# Sheet1.net
KiCad netlist of a schematic drawn in Altium Designer
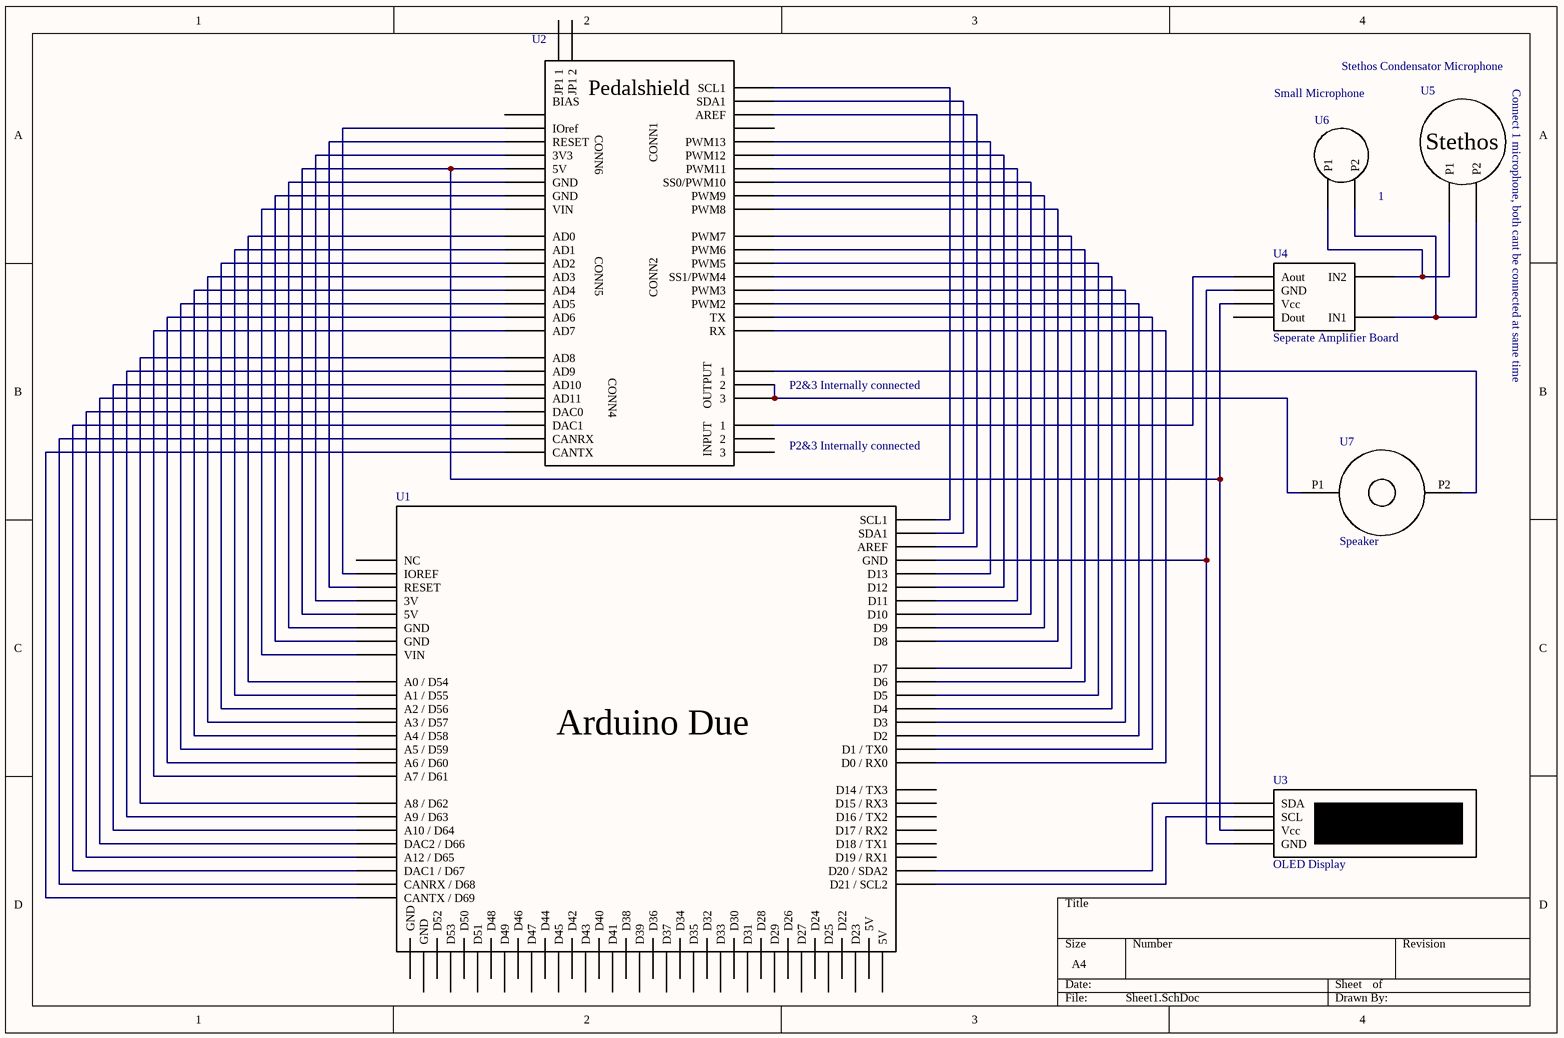
[diagram p0: Sheet1.SchDoc]

(export (version "E")
  (design (tool "Eeschema 10.0.6"))
  (components
    (comp (ref "U1") (value "Arduino Due") (libsource (lib "Schlib1") (part "Arduino Due")))
    (comp (ref "U2") (value "1") (libsource (lib "Schlib1") (part "Pedalshield")))
    (comp (ref "U3") (value "OLED Display") (libsource (lib "Schlib1") (part "OLED Display")))
    (comp (ref "U4")
      (value "Seperate Amplifier Board")
      (libsource (lib "Schlib1") (part "Seperate Amplifier Board"))
    )
    (comp (ref "U5")
      (value "Stethos Condensator Microphone")
      (libsource (lib "Schlib1") (part "Stethos Condensator Microphone"))
    )
    (comp (ref "U6") (value "Small Microphone") (libsource (lib "Schlib1") (part "Small Microphone")))
    (comp (ref "U7") (value "Speaker") (libsource (lib "Schlib1") (part "Speaker")))
  )
  (nets
    (net (code "1") (name "Net-(U1-3V)") (class "Default")
      (node (ref "U1") (pin "SDA5") (pinfunction "3V_SDA5") (pintype "passive"))
      (node (ref "U2") (pin "SDA103") (pinfunction "3V3_SDA103") (pintype "passive"))
    )
    (net (code "2") (name "Net-(U1-A0_{slash}_D54)") (class "Default")
      (node (ref "U1") (pin "SDA11") (pinfunction "A0_/_D54_SDA11") (pintype "passive"))
      (node (ref "U2") (pin "SDA108") (pinfunction "AD0_SDA108") (pintype "passive"))
    )
    (net (code "3") (name "Net-(U1-A1_{slash}_D55)") (class "Default")
      (node (ref "U1") (pin "SDA12") (pinfunction "A1_/_D55_SDA12") (pintype "passive"))
      (node (ref "U2") (pin "SDA109") (pinfunction "AD1_SDA109") (pintype "passive"))
    )
    (net (code "4") (name "Net-(U1-A2_{slash}_D56)") (class "Default")
      (node (ref "U1") (pin "SDA13") (pinfunction "A2_/_D56_SDA13") (pintype "passive"))
      (node (ref "U2") (pin "SDA110") (pinfunction "AD2_SDA110") (pintype "passive"))
    )
    (net (code "5") (name "Net-(U1-A3_{slash}_D57)") (class "Default")
      (node (ref "U1") (pin "SDA14") (pinfunction "A3_/_D57_SDA14") (pintype "passive"))
      (node (ref "U2") (pin "SDA111") (pinfunction "AD3_SDA111") (pintype "passive"))
    )
    (net (code "6") (name "Net-(U1-A4_{slash}_D58)") (class "Default")
      (node (ref "U1") (pin "SDA15") (pinfunction "A4_/_D58_SDA15") (pintype "passive"))
      (node (ref "U2") (pin "SDA112") (pinfunction "AD4_SDA112") (pintype "passive"))
    )
    (net (code "7") (name "Net-(U1-A5_{slash}_D59)") (class "Default")
      (node (ref "U1") (pin "SDA16") (pinfunction "A5_/_D59_SDA16") (pintype "passive"))
      (node (ref "U2") (pin "SDA113") (pinfunction "AD5_SDA113") (pintype "passive"))
    )
    (net (code "8") (name "Net-(U1-A6_{slash}_D60)") (class "Default")
      (node (ref "U1") (pin "SDA17") (pinfunction "A6_/_D60_SDA17") (pintype "passive"))
      (node (ref "U2") (pin "SDA114") (pinfunction "AD6_SDA114") (pintype "passive"))
    )
    (net (code "9") (name "Net-(U1-A7_{slash}_D61)") (class "Default")
      (node (ref "U1") (pin "SDA18") (pinfunction "A7_/_D61_SDA18") (pintype "passive"))
      (node (ref "U2") (pin "SDA115") (pinfunction "AD7_SDA115") (pintype "passive"))
    )
    (net (code "10") (name "Net-(U1-A8_{slash}_D62)") (class "Default")
      (node (ref "U1") (pin "SDA20") (pinfunction "A8_/_D62_SDA20") (pintype "passive"))
      (node (ref "U2") (pin "SDA97") (pinfunction "AD8_SDA97") (pintype "passive"))
    )
    (net (code "11") (name "Net-(U1-A9_{slash}_D63)") (class "Default")
      (node (ref "U1") (pin "SDA21") (pinfunction "A9_/_D63_SDA21") (pintype "passive"))
      (node (ref "U2") (pin "SDA96") (pinfunction "AD9_SDA96") (pintype "passive"))
    )
    (net (code "12") (name "Net-(U1-A10_{slash}_D64)") (class "Default")
      (node (ref "U1") (pin "SDA22") (pinfunction "A10_/_D64_SDA22") (pintype "passive"))
      (node (ref "U2") (pin "SDA95") (pinfunction "AD10_SDA95") (pintype "passive"))
    )
    (net (code "13") (name "Net-(U1-A12_{slash}_D65)") (class "Default")
      (node (ref "U1") (pin "SDA24") (pinfunction "A12_/_D65_SDA24") (pintype "passive"))
      (node (ref "U2") (pin "SDA93") (pinfunction "DAC0_SDA93") (pintype "passive"))
    )
    (net (code "14") (name "Net-(U1-CANRX_{slash}_D68)") (class "Default")
      (node (ref "U1") (pin "SDA26") (pinfunction "CANRX_/_D68_SDA26") (pintype "passive"))
      (node (ref "U2") (pin "SDA91") (pinfunction "CANRX_SDA91") (pintype "passive"))
    )
    (net (code "15") (name "Net-(U1-CANTX_{slash}_D69)") (class "Default")
      (node (ref "U1") (pin "SDA27") (pinfunction "CANTX_/_D69_SDA27") (pintype "passive"))
      (node (ref "U2") (pin "SDA90") (pinfunction "CANTX_SDA90") (pintype "passive"))
    )
    (net (code "16") (name "Net-(U1-D0_{slash}_RX0)") (class "Default")
      (node (ref "U1") (pin "29") (pinfunction "D0_/_RX0_29") (pintype "passive"))
      (node (ref "U2") (pin "SDA88") (pinfunction "RX_SDA88") (pintype "passive"))
    )
    (net (code "17") (name "Net-(U1-D1_{slash}_TX0)") (class "Default")
      (node (ref "U1") (pin "28") (pinfunction "D1_/_TX0_28") (pintype "passive"))
      (node (ref "U2") (pin "SDA87") (pinfunction "TX_SDA87") (pintype "passive"))
    )
    (net (code "18") (name "Net-(U1-D2)") (class "Default")
      (node (ref "U1") (pin "27") (pinfunction "D2_27") (pintype "passive"))
      (node (ref "U2") (pin "SDA118") (pinfunction "PWM2_SDA118") (pintype "passive"))
    )
    (net (code "19") (name "Net-(U1-D3)") (class "Default")
      (node (ref "U1") (pin "26") (pinfunction "D3_26") (pintype "passive"))
      (node (ref "U2") (pin "SDA86") (pinfunction "PWM3_SDA86") (pintype "passive"))
    )
    (net (code "20") (name "Net-(U1-D4)") (class "Default")
      (node (ref "U1") (pin "25") (pinfunction "D4_25") (pintype "passive"))
      (node (ref "U2") (pin "SDA85") (pinfunction "SS1/PWM4_SDA85") (pintype "passive"))
    )
    (net (code "21") (name "Net-(U1-D5)") (class "Default")
      (node (ref "U1") (pin "24") (pinfunction "D5_24") (pintype "passive"))
      (node (ref "U2") (pin "SDA84") (pinfunction "PWM5_SDA84") (pintype "passive"))
    )
    (net (code "22") (name "Net-(U1-D6)") (class "Default")
      (node (ref "U1") (pin "23") (pinfunction "D6_23") (pintype "passive"))
      (node (ref "U2") (pin "SDA83") (pinfunction "PWM6_SDA83") (pintype "passive"))
    )
    (net (code "23") (name "Net-(U1-D7)") (class "Default")
      (node (ref "U1") (pin "22") (pinfunction "D7_22") (pintype "passive"))
      (node (ref "U2") (pin "SDA82") (pinfunction "PWM7_SDA82") (pintype "passive"))
    )
    (net (code "24") (name "Net-(U1-D8)") (class "Default")
      (node (ref "U1") (pin "21") (pinfunction "D8_21") (pintype "passive"))
      (node (ref "U2") (pin "SDA117") (pinfunction "PWM8_SDA117") (pintype "passive"))
    )
    (net (code "25") (name "Net-(U1-D9)") (class "Default")
      (node (ref "U1") (pin "20") (pinfunction "D9_20") (pintype "passive"))
      (node (ref "U2") (pin "SDA116") (pinfunction "PWM9_SDA116") (pintype "passive"))
    )
    (net (code "26") (name "Net-(U1-D10)") (class "Default")
      (node (ref "U1") (pin "19") (pinfunction "D10_19") (pintype "passive"))
      (node (ref "U2") (pin "SDA81") (pinfunction "SS0/PWM10_SDA81") (pintype "passive"))
    )
    (net (code "27") (name "Net-(U1-D11)") (class "Default")
      (node (ref "U1") (pin "18") (pinfunction "D11_18") (pintype "passive"))
      (node (ref "U2") (pin "SDA80") (pinfunction "PWM11_SDA80") (pintype "passive"))
    )
    (net (code "28") (name "Net-(U1-D12)") (class "Default")
      (node (ref "U1") (pin "17") (pinfunction "D12_17") (pintype "passive"))
      (node (ref "U2") (pin "SDA79") (pinfunction "PWM12_SDA79") (pintype "passive"))
    )
    (net (code "29") (name "Net-(U1-D13)") (class "Default")
      (node (ref "U1") (pin "16") (pinfunction "D13_16") (pintype "passive"))
      (node (ref "U2") (pin "SDA78") (pinfunction "PWM13_SDA78") (pintype "passive"))
    )
    (net (code "30") (name "Net-(U1-D20_{slash}_SDA2)") (class "Default")
      (node (ref "U1") (pin "36") (pinfunction "D20_/_SDA2_36") (pintype "passive"))
      (node (ref "U3") (pin "SDA69") (pinfunction "SDA_SDA69") (pintype "passive"))
    )
    (net (code "31") (name "Net-(U1-D21_{slash}_SCL2)") (class "Default")
      (node (ref "U1") (pin "37") (pinfunction "D21_/_SCL2_37") (pintype "passive"))
      (node (ref "U3") (pin "SDA70") (pinfunction "SCL_SDA70") (pintype "passive"))
    )
    (net (code "32") (name "Net-(U1-DAC1_{slash}_D67)") (class "Default")
      (node (ref "U1") (pin "SDA25") (pinfunction "DAC1_/_D67_SDA25") (pintype "passive"))
      (node (ref "U2") (pin "SDA92") (pinfunction "DAC1_SDA92") (pintype "passive"))
    )
    (net (code "33") (name "Net-(U1-DAC2_{slash}_D66)") (class "Default")
      (node (ref "U1") (pin "SDA23") (pinfunction "DAC2_/_D66_SDA23") (pintype "passive"))
      (node (ref "U2") (pin "SDA94") (pinfunction "AD11_SDA94") (pintype "passive"))
    )
    (net (code "34") (name "Net-(U1-GND-PadSDA7)") (class "Default")
      (node (ref "U1") (pin "SDA7") (pinfunction "GND_SDA7") (pintype "passive"))
      (node (ref "U2") (pin "SDA105") (pinfunction "GND_SDA105") (pintype "passive"))
    )
    (net (code "35") (name "Net-(U1-GND-PadSDA8)") (class "Default")
      (node (ref "U1") (pin "SDA8") (pinfunction "GND_SDA8") (pintype "passive"))
      (node (ref "U2") (pin "SDA106") (pinfunction "GND_SDA106") (pintype "passive"))
    )
    (net (code "36") (name "Net-(U1-IOREF)") (class "Default")
      (node (ref "U1") (pin "SDA3") (pinfunction "IOREF_SDA3") (pintype "passive"))
      (node (ref "U2") (pin "SDA101") (pinfunction "IOref_SDA101") (pintype "passive"))
    )
    (net (code "37") (name "Net-(U1-RESET)") (class "Default")
      (node (ref "U1") (pin "SDA4") (pinfunction "RESET_SDA4") (pintype "passive"))
      (node (ref "U2") (pin "SDA102") (pinfunction "RESET_SDA102") (pintype "passive"))
    )
    (net (code "38") (name "Net-(U1-VIN)") (class "Default")
      (node (ref "U1") (pin "SDA9") (pinfunction "VIN_SDA9") (pintype "passive"))
      (node (ref "U2") (pin "SDA107") (pinfunction "VIN_SDA107") (pintype "passive"))
    )
    (net (code "39") (name "Net-(U2-1-PadSDA119)") (class "Default")
      (node (ref "U2") (pin "SDA119") (pinfunction "1_SDA119") (pintype "passive"))
      (node (ref "U7") (pin "P2") (pinfunction "P2_P2") (pintype "passive"))
    )
    (net (code "40") (name "Net-(U2-2-PadSDA120)") (class "Default")
      (node (ref "U2") (pin "SDA120") (pinfunction "2_SDA120") (pintype "passive"))
      (node (ref "U2") (pin "SDA121") (pinfunction "3_SDA121") (pintype "passive"))
      (node (ref "U7") (pin "P1") (pinfunction "P1_P1") (pintype "passive"))
    )
    (net (code "41") (name "Net-(U2-5V)") (class "Default")
      (node (ref "U1") (pin "SDA6") (pinfunction "5V_SDA6") (pintype "passive"))
      (node (ref "U2") (pin "SDA104") (pinfunction "5V_SDA104") (pintype "passive"))
      (node (ref "U3") (pin "SDA71") (pinfunction "Vcc_SDA71") (pintype "passive"))
      (node (ref "U4") (pin "SDA64") (pinfunction "Vcc_SDA64") (pintype "passive"))
    )
    (net (code "42") (name "Net-(U2-AREF)") (class "Default")
      (node (ref "U1") (pin "AREF") (pinfunction "AREF_AREF") (pintype "passive"))
      (node (ref "U2") (pin "SDA76") (pinfunction "AREF_SDA76") (pintype "passive"))
    )
    (net (code "43") (name "Net-(U2-SCL1)") (class "Default")
      (node (ref "U1") (pin "SCL1") (pinfunction "SCL1_SCL1") (pintype "passive"))
      (node (ref "U2") (pin "SDA74") (pinfunction "SCL1_SDA74") (pintype "passive"))
    )
    (net (code "44") (name "Net-(U2-SDA1)") (class "Default")
      (node (ref "U1") (pin "SDA1") (pinfunction "SDA1_SDA1") (pintype "passive"))
      (node (ref "U2") (pin "SDA75") (pinfunction "SDA1_SDA75") (pintype "passive"))
    )
    (net (code "45") (name "Net-(U3-GND)") (class "Default")
      (node (ref "U1") (pin "GND") (pinfunction "GND_GND") (pintype "passive"))
      (node (ref "U3") (pin "SDA72") (pinfunction "GND_SDA72") (pintype "passive"))
      (node (ref "U4") (pin "SDA65") (pinfunction "GND_SDA65") (pintype "passive"))
    )
    (net (code "46") (name "Net-(U4-Aout)") (class "Default")
      (node (ref "U2") (pin "SDA122") (pinfunction "1_SDA122") (pintype "passive"))
      (node (ref "U4") (pin "SDA66") (pinfunction "Aout_SDA66") (pintype "passive"))
    )
    (net (code "47") (name "Net-(U4-IN1)") (class "Default")
      (node (ref "U4") (pin "SDA67") (pinfunction "IN1_SDA67") (pintype "passive"))
      (node (ref "U5") (pin "SDA67") (pinfunction "P2_SDA67") (pintype "passive"))
      (node (ref "U6") (pin "SDA67") (pinfunction "P2_SDA67") (pintype "passive"))
    )
    (net (code "48") (name "Net-(U4-IN2)") (class "Default")
      (node (ref "U4") (pin "SDA68") (pinfunction "IN2_SDA68") (pintype "passive"))
      (node (ref "U5") (pin "SDA68") (pinfunction "P1_SDA68") (pintype "passive"))
      (node (ref "U6") (pin "SDA68") (pinfunction "P1_SDA68") (pintype "passive"))
    )
    (net (code "49") (name "unconnected-(U1-5V-PadSDA28)") (class "Default")
      (node (ref "U1") (pin "SDA28") (pinfunction "5V_SDA28") (pintype "passive"))
    )
    (net (code "50") (name "unconnected-(U1-5V-PadSDA29)") (class "Default")
      (node (ref "U1") (pin "SDA29") (pinfunction "5V_SDA29") (pintype "passive"))
    )
    (net (code "51") (name "unconnected-(U1-D14_{slash}_TX3-Pad30)") (class "Default")
      (node (ref "U1") (pin "30") (pinfunction "D14_/_TX3_30") (pintype "passive"))
    )
    (net (code "52") (name "unconnected-(U1-D15_{slash}_RX3-Pad31)") (class "Default")
      (node (ref "U1") (pin "31") (pinfunction "D15_/_RX3_31") (pintype "passive"))
    )
    (net (code "53") (name "unconnected-(U1-D16_{slash}_TX2-Pad32)") (class "Default")
      (node (ref "U1") (pin "32") (pinfunction "D16_/_TX2_32") (pintype "passive"))
    )
    (net (code "54") (name "unconnected-(U1-D17_{slash}_RX2-Pad33)") (class "Default")
      (node (ref "U1") (pin "33") (pinfunction "D17_/_RX2_33") (pintype "passive"))
    )
    (net (code "55") (name "unconnected-(U1-D18_{slash}_TX1-Pad34)") (class "Default")
      (node (ref "U1") (pin "34") (pinfunction "D18_/_TX1_34") (pintype "passive"))
    )
    (net (code "56") (name "unconnected-(U1-D19_{slash}_RX1-Pad35)") (class "Default")
      (node (ref "U1") (pin "35") (pinfunction "D19_/_RX1_35") (pintype "passive"))
    )
    (net (code "57") (name "unconnected-(U1-D22-PadSDA31)") (class "Default")
      (node (ref "U1") (pin "SDA31") (pinfunction "D22_SDA31") (pintype "passive"))
    )
    (net (code "58") (name "unconnected-(U1-D23-PadSDA30)") (class "Default")
      (node (ref "U1") (pin "SDA30") (pinfunction "D23_SDA30") (pintype "passive"))
    )
    (net (code "59") (name "unconnected-(U1-D24-PadSDA33)") (class "Default")
      (node (ref "U1") (pin "SDA33") (pinfunction "D24_SDA33") (pintype "passive"))
    )
    (net (code "60") (name "unconnected-(U1-D25-PadSDA32)") (class "Default")
      (node (ref "U1") (pin "SDA32") (pinfunction "D25_SDA32") (pintype "passive"))
    )
    (net (code "61") (name "unconnected-(U1-D26-PadSDA35)") (class "Default")
      (node (ref "U1") (pin "SDA35") (pinfunction "D26_SDA35") (pintype "passive"))
    )
    (net (code "62") (name "unconnected-(U1-D27-PadSDA34)") (class "Default")
      (node (ref "U1") (pin "SDA34") (pinfunction "D27_SDA34") (pintype "passive"))
    )
    (net (code "63") (name "unconnected-(U1-D28-PadSDA37)") (class "Default")
      (node (ref "U1") (pin "SDA37") (pinfunction "D28_SDA37") (pintype "passive"))
    )
    (net (code "64") (name "unconnected-(U1-D29-PadSDA36)") (class "Default")
      (node (ref "U1") (pin "SDA36") (pinfunction "D29_SDA36") (pintype "passive"))
    )
    (net (code "65") (name "unconnected-(U1-D30-PadSDA39)") (class "Default")
      (node (ref "U1") (pin "SDA39") (pinfunction "D30_SDA39") (pintype "passive"))
    )
    (net (code "66") (name "unconnected-(U1-D31-PadSDA38)") (class "Default")
      (node (ref "U1") (pin "SDA38") (pinfunction "D31_SDA38") (pintype "passive"))
    )
    (net (code "67") (name "unconnected-(U1-D32-PadSDA41)") (class "Default")
      (node (ref "U1") (pin "SDA41") (pinfunction "D32_SDA41") (pintype "passive"))
    )
    (net (code "68") (name "unconnected-(U1-D33-PadSDA40)") (class "Default")
      (node (ref "U1") (pin "SDA40") (pinfunction "D33_SDA40") (pintype "passive"))
    )
    (net (code "69") (name "unconnected-(U1-D34-PadSDA43)") (class "Default")
      (node (ref "U1") (pin "SDA43") (pinfunction "D34_SDA43") (pintype "passive"))
    )
    (net (code "70") (name "unconnected-(U1-D35-PadSDA42)") (class "Default")
      (node (ref "U1") (pin "SDA42") (pinfunction "D35_SDA42") (pintype "passive"))
    )
    (net (code "71") (name "unconnected-(U1-D36-PadSDA45)") (class "Default")
      (node (ref "U1") (pin "SDA45") (pinfunction "D36_SDA45") (pintype "passive"))
    )
    (net (code "72") (name "unconnected-(U1-D37-PadSDA44)") (class "Default")
      (node (ref "U1") (pin "SDA44") (pinfunction "D37_SDA44") (pintype "passive"))
    )
    (net (code "73") (name "unconnected-(U1-D38-PadSDA47)") (class "Default")
      (node (ref "U1") (pin "SDA47") (pinfunction "D38_SDA47") (pintype "passive"))
    )
    (net (code "74") (name "unconnected-(U1-D39-PadSDA46)") (class "Default")
      (node (ref "U1") (pin "SDA46") (pinfunction "D39_SDA46") (pintype "passive"))
    )
    (net (code "75") (name "unconnected-(U1-D40-PadSDA56)") (class "Default")
      (node (ref "U1") (pin "SDA56") (pinfunction "D40_SDA56") (pintype "passive"))
    )
    (net (code "76") (name "unconnected-(U1-D41-PadSDA48)") (class "Default")
      (node (ref "U1") (pin "SDA48") (pinfunction "D41_SDA48") (pintype "passive"))
    )
    (net (code "77") (name "unconnected-(U1-D42-PadSDA57)") (class "Default")
      (node (ref "U1") (pin "SDA57") (pinfunction "D42_SDA57") (pintype "passive"))
    )
    (net (code "78") (name "unconnected-(U1-D43-PadSDA49)") (class "Default")
      (node (ref "U1") (pin "SDA49") (pinfunction "D43_SDA49") (pintype "passive"))
    )
    (net (code "79") (name "unconnected-(U1-D44-PadSDA58)") (class "Default")
      (node (ref "U1") (pin "SDA58") (pinfunction "D44_SDA58") (pintype "passive"))
    )
    (net (code "80") (name "unconnected-(U1-D45-PadSDA50)") (class "Default")
      (node (ref "U1") (pin "SDA50") (pinfunction "D45_SDA50") (pintype "passive"))
    )
    (net (code "81") (name "unconnected-(U1-D46-PadSDA59)") (class "Default")
      (node (ref "U1") (pin "SDA59") (pinfunction "D46_SDA59") (pintype "passive"))
    )
    (net (code "82") (name "unconnected-(U1-D47-PadSDA51)") (class "Default")
      (node (ref "U1") (pin "SDA51") (pinfunction "D47_SDA51") (pintype "passive"))
    )
    (net (code "83") (name "unconnected-(U1-D48-PadSDA60)") (class "Default")
      (node (ref "U1") (pin "SDA60") (pinfunction "D48_SDA60") (pintype "passive"))
    )
    (net (code "84") (name "unconnected-(U1-D49-PadSDA52)") (class "Default")
      (node (ref "U1") (pin "SDA52") (pinfunction "D49_SDA52") (pintype "passive"))
    )
    (net (code "85") (name "unconnected-(U1-D50-PadSDA61)") (class "Default")
      (node (ref "U1") (pin "SDA61") (pinfunction "D50_SDA61") (pintype "passive"))
    )
    (net (code "86") (name "unconnected-(U1-D51-PadSDA53)") (class "Default")
      (node (ref "U1") (pin "SDA53") (pinfunction "D51_SDA53") (pintype "passive"))
    )
    (net (code "87") (name "unconnected-(U1-D52-PadSDA62)") (class "Default")
      (node (ref "U1") (pin "SDA62") (pinfunction "D52_SDA62") (pintype "passive"))
    )
    (net (code "88") (name "unconnected-(U1-D53-PadSDA54)") (class "Default")
      (node (ref "U1") (pin "SDA54") (pinfunction "D53_SDA54") (pintype "passive"))
    )
    (net (code "89") (name "unconnected-(U1-GND-PadSDA55)") (class "Default")
      (node (ref "U1") (pin "SDA55") (pinfunction "GND_SDA55") (pintype "passive"))
    )
    (net (code "90") (name "unconnected-(U1-GND-PadSDA55)_1") (class "Default")
      (node (ref "U1") (pin "SDA55") (pinfunction "GND_SDA55") (pintype "passive"))
    )
    (net (code "91") (name "unconnected-(U1-NC-PadSDA2)") (class "Default")
      (node (ref "U1") (pin "SDA2") (pinfunction "NC_SDA2") (pintype "passive"))
    )
    (net (code "92") (name "unconnected-(U2-2-PadSDA123)") (class "Default")
      (node (ref "U2") (pin "SDA123") (pinfunction "2_SDA123") (pintype "passive"))
    )
    (net (code "93") (name "unconnected-(U2-3-PadSDA124)") (class "Default")
      (node (ref "U2") (pin "SDA124") (pinfunction "3_SDA124") (pintype "passive"))
    )
    (net (code "94") (name "unconnected-(U2-JP1_1-PadSDA98)") (class "Default")
      (node (ref "U2") (pin "SDA98") (pinfunction "JP1_1_SDA98") (pintype "passive"))
    )
    (net (code "95") (name "unconnected-(U2-JP1_2-PadSDA99)") (class "Default")
      (node (ref "U2") (pin "SDA99") (pinfunction "JP1_2_SDA99") (pintype "passive"))
    )
    (net (code "96") (name "unconnected-(U2-PadSDA77)") (class "Default")
      (node (ref "U2") (pin "SDA77") (pinfunction "SDA77_SDA77") (pintype "passive"))
    )
    (net (code "97") (name "unconnected-(U2-PadSDA100)") (class "Default")
      (node (ref "U2") (pin "SDA100") (pinfunction "SDA100_SDA100") (pintype "passive"))
    )
    (net (code "98") (name "unconnected-(U4-Dout-PadSDA63)") (class "Default")
      (node (ref "U4") (pin "SDA63") (pinfunction "Dout_SDA63") (pintype "passive"))
    )
  )
)
